# SuperPET_OS9_MMU_3_0.net
KiCad netlist of a schematic drawn in EAGLE
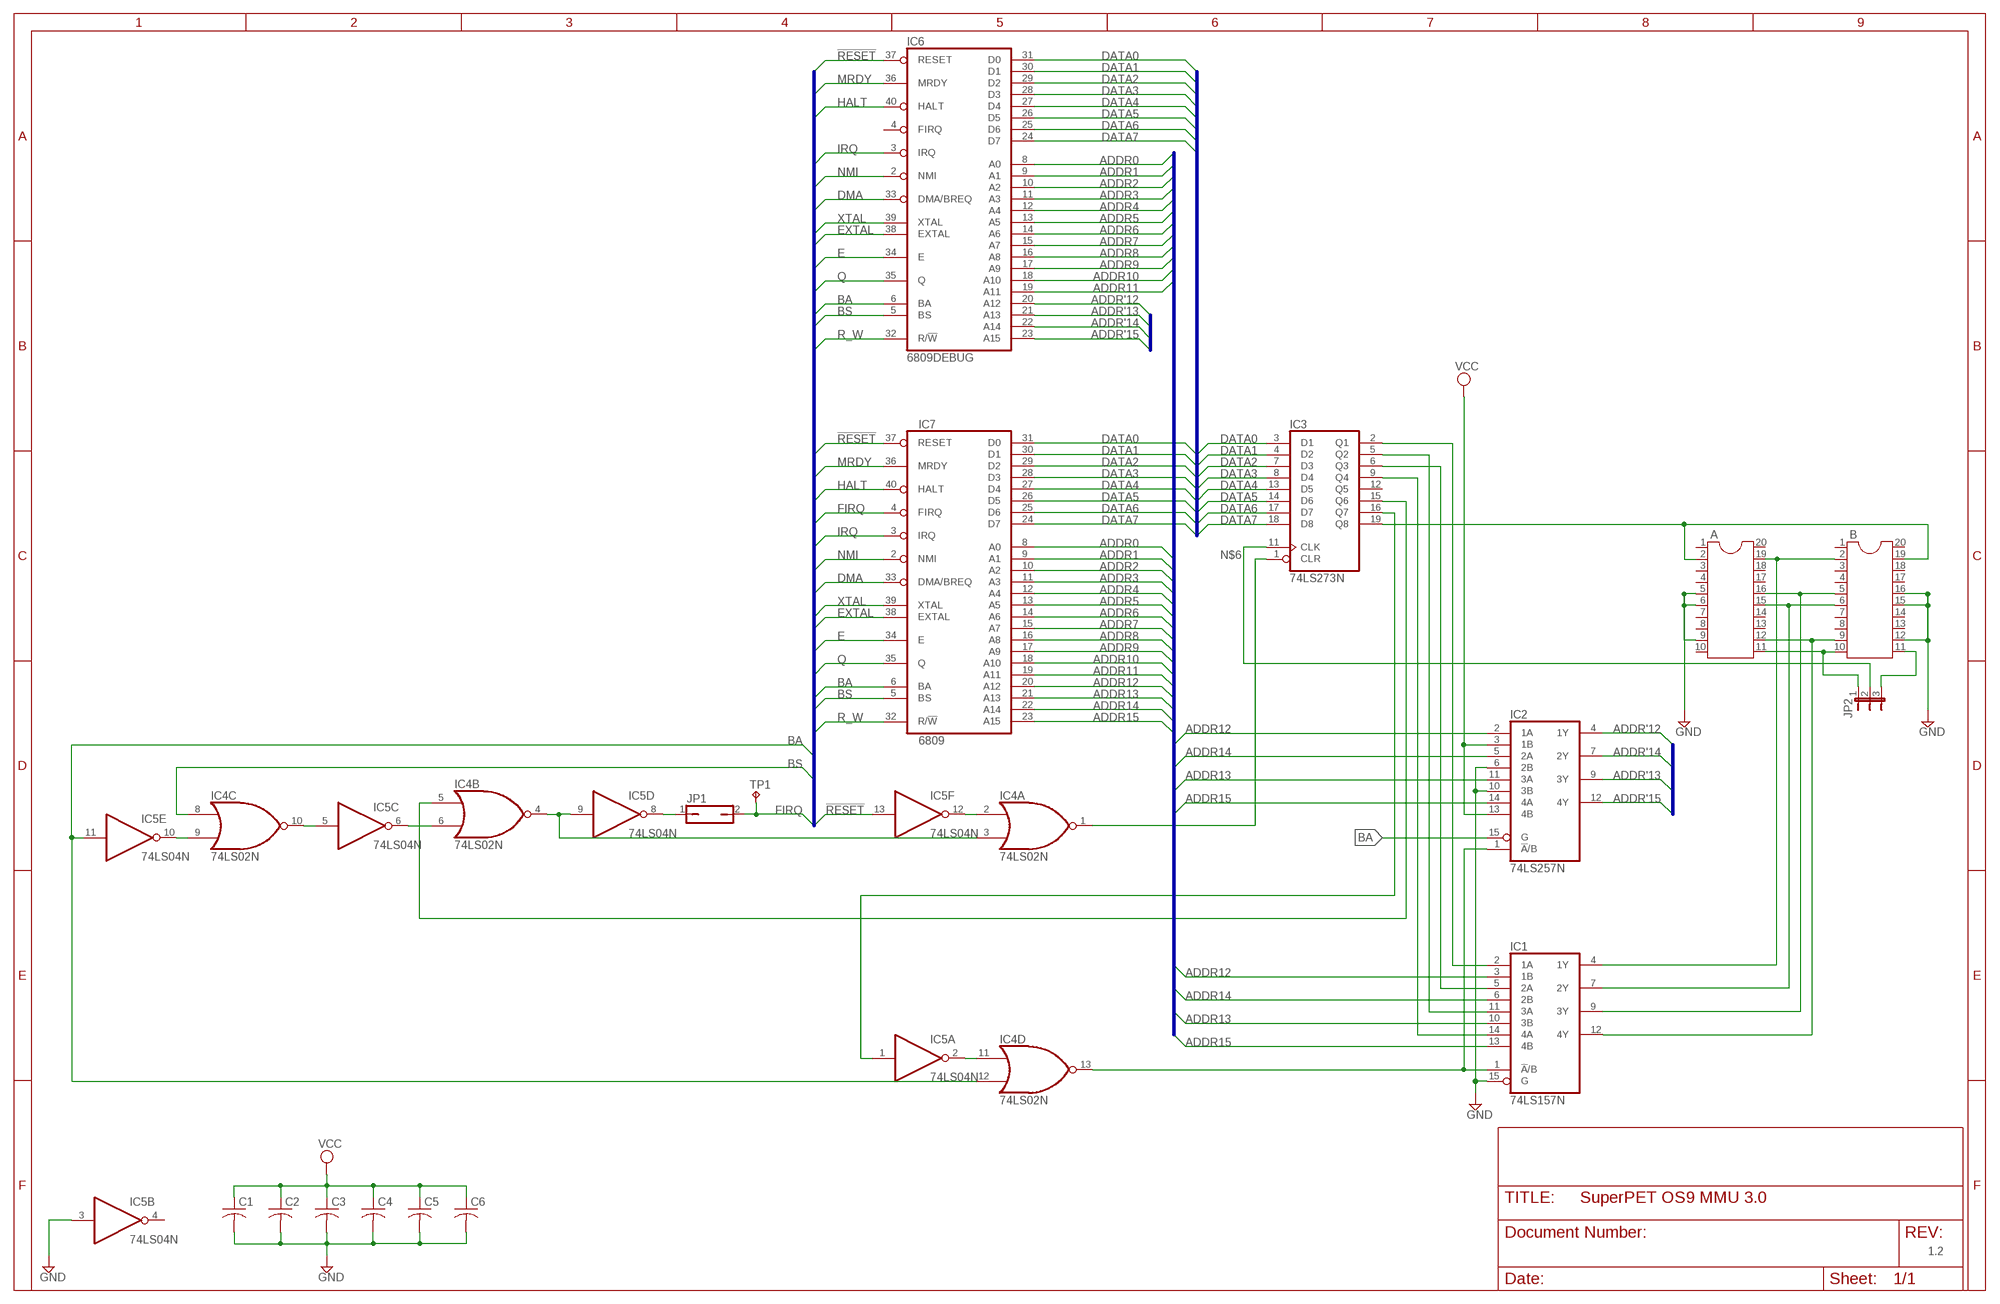
[diagram p0: schematic, sheet 1]

(export (version "E")
  (design (tool "Eeschema 10.0.6"))
  (components
    (comp (ref "A")
      (value "DIL20S")
      (footprint "eagle-import:SOCKET-20")
      (libsource (lib "eagle-import") (part "DIL20S"))
    )
    (comp (ref "B")
      (value "DIL20S")
      (footprint "eagle-import:SOCKET-20")
      (libsource (lib "eagle-import") (part "DIL20S"))
    )
    (comp (ref "C1")
      (value "C-US050-025X075")
      (footprint "eagle-import:C050-025X075")
      (libsource (lib "eagle-import") (part "C-US050-025X075"))
    )
    (comp (ref "C2")
      (value "C-US050-025X075")
      (footprint "eagle-import:C050-025X075")
      (libsource (lib "eagle-import") (part "C-US050-025X075"))
    )
    (comp (ref "C3")
      (value "C-US050-025X075")
      (footprint "eagle-import:C050-025X075")
      (libsource (lib "eagle-import") (part "C-US050-025X075"))
    )
    (comp (ref "C4")
      (value "C-US050-025X075")
      (footprint "eagle-import:C050-025X075")
      (libsource (lib "eagle-import") (part "C-US050-025X075"))
    )
    (comp (ref "C5")
      (value "C-US050-025X075")
      (footprint "eagle-import:C050-025X075")
      (libsource (lib "eagle-import") (part "C-US050-025X075"))
    )
    (comp (ref "C6")
      (value "C-US050-025X075")
      (footprint "eagle-import:C050-025X075")
      (libsource (lib "eagle-import") (part "C-US050-025X075"))
    )
    (comp (ref "IC1")
      (value "74LS157N")
      (footprint "eagle-import:DIL16")
      (libsource (lib "eagle-import") (part "74157NLS"))
    )
    (comp (ref "IC2")
      (value "74LS257N")
      (footprint "eagle-import:DIL16")
      (libsource (lib "eagle-import") (part "74257NLS"))
    )
    (comp (ref "IC3")
      (value "74LS273N")
      (footprint "eagle-import:DIL20")
      (libsource (lib "eagle-import") (part "74273N"))
    )
    (comp (ref "IC4")
      (value "74LS02N")
      (footprint "eagle-import:DIL14")
      (libsource (lib "eagle-import") (part "7402NLS"))
    )
    (comp (ref "IC5")
      (value "74LS04N")
      (footprint "eagle-import:DIL14")
      (libsource (lib "eagle-import") (part "7404NLS"))
    )
    (comp (ref "IC6")
      (value "6809DEBUG")
      (footprint "eagle-import:DIL40")
      (libsource (lib "eagle-import") (part "6809DEBUG"))
    )
    (comp (ref "IC7")
      (value "6809")
      (footprint "eagle-import:DIL40")
      (libsource (lib "eagle-import") (part "6809"))
    )
    (comp (ref "JP1")
      (value "JP1Q")
      (footprint "eagle-import:JP1")
      (libsource (lib "eagle-import") (part "JP1Q"))
    )
    (comp (ref "JP2")
      (value "JP2E")
      (footprint "eagle-import:JP2")
      (libsource (lib "eagle-import") (part "JP2E"))
    )
    (comp (ref "TP1")
      (value "TPPAD1-13")
      (footprint "eagle-import:P1-13")
      (libsource (lib "eagle-import") (part "TPPAD1-13"))
    )
  )
  (nets
    (net (code "1") (name "/ADDR'12") (class "Default")
      (node (ref "IC2") (pin "4") (pinfunction "1Y_4") (pintype "tri_state"))
      (node (ref "IC6") (pin "20") (pinfunction "A12_20") (pintype "tri_state"))
    )
    (net (code "2") (name "/ADDR'13") (class "Default")
      (node (ref "IC2") (pin "9") (pinfunction "3Y_9") (pintype "tri_state"))
      (node (ref "IC6") (pin "21") (pinfunction "A13_21") (pintype "tri_state"))
    )
    (net (code "3") (name "/ADDR'14") (class "Default")
      (node (ref "IC2") (pin "7") (pinfunction "2Y_7") (pintype "tri_state"))
      (node (ref "IC6") (pin "22") (pinfunction "A14_22") (pintype "tri_state"))
    )
    (net (code "4") (name "/ADDR'15") (class "Default")
      (node (ref "IC2") (pin "12") (pinfunction "4Y_12") (pintype "tri_state"))
      (node (ref "IC6") (pin "23") (pinfunction "A15_23") (pintype "tri_state"))
    )
    (net (code "5") (name "/ADDR0") (class "Default")
      (node (ref "IC6") (pin "8") (pinfunction "A0_8") (pintype "tri_state"))
      (node (ref "IC7") (pin "8") (pinfunction "A0_8") (pintype "tri_state"))
    )
    (net (code "6") (name "/ADDR1") (class "Default")
      (node (ref "IC6") (pin "9") (pinfunction "A1_9") (pintype "tri_state"))
      (node (ref "IC7") (pin "9") (pinfunction "A1_9") (pintype "tri_state"))
    )
    (net (code "7") (name "/ADDR2") (class "Default")
      (node (ref "IC6") (pin "10") (pinfunction "A2_10") (pintype "tri_state"))
      (node (ref "IC7") (pin "10") (pinfunction "A2_10") (pintype "tri_state"))
    )
    (net (code "8") (name "/ADDR3") (class "Default")
      (node (ref "IC6") (pin "11") (pinfunction "A3_11") (pintype "tri_state"))
      (node (ref "IC7") (pin "11") (pinfunction "A3_11") (pintype "tri_state"))
    )
    (net (code "9") (name "/ADDR4") (class "Default")
      (node (ref "IC6") (pin "12") (pinfunction "A4_12") (pintype "tri_state"))
      (node (ref "IC7") (pin "12") (pinfunction "A4_12") (pintype "tri_state"))
    )
    (net (code "10") (name "/ADDR5") (class "Default")
      (node (ref "IC6") (pin "13") (pinfunction "A5_13") (pintype "tri_state"))
      (node (ref "IC7") (pin "13") (pinfunction "A5_13") (pintype "tri_state"))
    )
    (net (code "11") (name "/ADDR6") (class "Default")
      (node (ref "IC6") (pin "14") (pinfunction "A6_14") (pintype "tri_state"))
      (node (ref "IC7") (pin "14") (pinfunction "A6_14") (pintype "tri_state"))
    )
    (net (code "12") (name "/ADDR7") (class "Default")
      (node (ref "IC6") (pin "15") (pinfunction "A7_15") (pintype "tri_state"))
      (node (ref "IC7") (pin "15") (pinfunction "A7_15") (pintype "tri_state"))
    )
    (net (code "13") (name "/ADDR8") (class "Default")
      (node (ref "IC6") (pin "16") (pinfunction "A8_16") (pintype "tri_state"))
      (node (ref "IC7") (pin "16") (pinfunction "A8_16") (pintype "tri_state"))
    )
    (net (code "14") (name "/ADDR9") (class "Default")
      (node (ref "IC6") (pin "17") (pinfunction "A9_17") (pintype "tri_state"))
      (node (ref "IC7") (pin "17") (pinfunction "A9_17") (pintype "tri_state"))
    )
    (net (code "15") (name "/ADDR10") (class "Default")
      (node (ref "IC6") (pin "18") (pinfunction "A10_18") (pintype "tri_state"))
      (node (ref "IC7") (pin "18") (pinfunction "A10_18") (pintype "tri_state"))
    )
    (net (code "16") (name "/ADDR11") (class "Default")
      (node (ref "IC6") (pin "19") (pinfunction "A11_19") (pintype "tri_state"))
      (node (ref "IC7") (pin "19") (pinfunction "A11_19") (pintype "tri_state"))
    )
    (net (code "17") (name "/ADDR12") (class "Default")
      (node (ref "IC1") (pin "3") (pinfunction "1B_3") (pintype "input"))
      (node (ref "IC2") (pin "2") (pinfunction "1A_2") (pintype "input"))
      (node (ref "IC7") (pin "20") (pinfunction "A12_20") (pintype "tri_state"))
    )
    (net (code "18") (name "/ADDR13") (class "Default")
      (node (ref "IC1") (pin "10") (pinfunction "3B_10") (pintype "input"))
      (node (ref "IC2") (pin "11") (pinfunction "3A_11") (pintype "input"))
      (node (ref "IC7") (pin "21") (pinfunction "A13_21") (pintype "tri_state"))
    )
    (net (code "19") (name "/ADDR14") (class "Default")
      (node (ref "IC1") (pin "6") (pinfunction "2B_6") (pintype "input"))
      (node (ref "IC2") (pin "5") (pinfunction "2A_5") (pintype "input"))
      (node (ref "IC7") (pin "22") (pinfunction "A14_22") (pintype "tri_state"))
    )
    (net (code "20") (name "/ADDR15") (class "Default")
      (node (ref "IC1") (pin "13") (pinfunction "4B_13") (pintype "input"))
      (node (ref "IC2") (pin "14") (pinfunction "4A_14") (pintype "input"))
      (node (ref "IC7") (pin "23") (pinfunction "A15_23") (pintype "tri_state"))
    )
    (net (code "21") (name "/BS") (class "Default")
      (node (ref "IC4") (pin "8") (pinfunction "I0_8") (pintype "input"))
      (node (ref "IC6") (pin "5") (pinfunction "BS_5") (pintype "input"))
      (node (ref "IC7") (pin "5") (pinfunction "BS_5") (pintype "output"))
    )
    (net (code "22") (name "/DATA0") (class "Default")
      (node (ref "IC3") (pin "3") (pinfunction "D1_3") (pintype "input"))
      (node (ref "IC6") (pin "31") (pinfunction "D0_31") (pintype "bidirectional"))
      (node (ref "IC7") (pin "31") (pinfunction "D0_31") (pintype "bidirectional"))
    )
    (net (code "23") (name "/DATA1") (class "Default")
      (node (ref "IC3") (pin "4") (pinfunction "D2_4") (pintype "input"))
      (node (ref "IC6") (pin "30") (pinfunction "D1_30") (pintype "bidirectional"))
      (node (ref "IC7") (pin "30") (pinfunction "D1_30") (pintype "bidirectional"))
    )
    (net (code "24") (name "/DATA2") (class "Default")
      (node (ref "IC3") (pin "7") (pinfunction "D3_7") (pintype "input"))
      (node (ref "IC6") (pin "29") (pinfunction "D2_29") (pintype "bidirectional"))
      (node (ref "IC7") (pin "29") (pinfunction "D2_29") (pintype "bidirectional"))
    )
    (net (code "25") (name "/DATA3") (class "Default")
      (node (ref "IC3") (pin "8") (pinfunction "D4_8") (pintype "input"))
      (node (ref "IC6") (pin "28") (pinfunction "D3_28") (pintype "bidirectional"))
      (node (ref "IC7") (pin "28") (pinfunction "D3_28") (pintype "bidirectional"))
    )
    (net (code "26") (name "/DATA4") (class "Default")
      (node (ref "IC3") (pin "13") (pinfunction "D5_13") (pintype "input"))
      (node (ref "IC6") (pin "27") (pinfunction "D4_27") (pintype "bidirectional"))
      (node (ref "IC7") (pin "27") (pinfunction "D4_27") (pintype "bidirectional"))
    )
    (net (code "27") (name "/DATA5") (class "Default")
      (node (ref "IC3") (pin "14") (pinfunction "D6_14") (pintype "input"))
      (node (ref "IC6") (pin "26") (pinfunction "D5_26") (pintype "bidirectional"))
      (node (ref "IC7") (pin "26") (pinfunction "D5_26") (pintype "bidirectional"))
    )
    (net (code "28") (name "/DATA6") (class "Default")
      (node (ref "IC3") (pin "17") (pinfunction "D7_17") (pintype "input"))
      (node (ref "IC6") (pin "25") (pinfunction "D6_25") (pintype "bidirectional"))
      (node (ref "IC7") (pin "25") (pinfunction "D6_25") (pintype "bidirectional"))
    )
    (net (code "29") (name "/DATA7") (class "Default")
      (node (ref "IC3") (pin "18") (pinfunction "D8_18") (pintype "input"))
      (node (ref "IC6") (pin "24") (pinfunction "D7_24") (pintype "bidirectional"))
      (node (ref "IC7") (pin "24") (pinfunction "D7_24") (pintype "bidirectional"))
    )
    (net (code "30") (name "/DMA") (class "Default")
      (node (ref "IC6") (pin "33") (pinfunction "DMA/BREQ_33") (pintype "output"))
      (node (ref "IC7") (pin "33") (pinfunction "DMA/BREQ_33") (pintype "input"))
    )
    (net (code "31") (name "/E") (class "Default")
      (node (ref "IC6") (pin "34") (pinfunction "E_34") (pintype "input"))
      (node (ref "IC7") (pin "34") (pinfunction "E_34") (pintype "output"))
    )
    (net (code "32") (name "/EXTAL") (class "Default")
      (node (ref "IC6") (pin "38") (pinfunction "EXTAL_38") (pintype "output"))
      (node (ref "IC7") (pin "38") (pinfunction "EXTAL_38") (pintype "input"))
    )
    (net (code "33") (name "/FIRQ") (class "Default")
      (node (ref "IC7") (pin "4") (pinfunction "FIRQ_4") (pintype "input"))
      (node (ref "JP1") (pin "2") (pinfunction "2_2") (pintype "passive"))
      (node (ref "TP1") (pin "1") (pinfunction "TP_1") (pintype "input"))
    )
    (net (code "34") (name "/HALT") (class "Default")
      (node (ref "IC6") (pin "40") (pinfunction "HALT_40") (pintype "output"))
      (node (ref "IC7") (pin "40") (pinfunction "HALT_40") (pintype "input"))
    )
    (net (code "35") (name "/IRQ") (class "Default")
      (node (ref "IC6") (pin "3") (pinfunction "IRQ_3") (pintype "output"))
      (node (ref "IC7") (pin "3") (pinfunction "IRQ_3") (pintype "input"))
    )
    (net (code "36") (name "/MRDY") (class "Default")
      (node (ref "IC6") (pin "36") (pinfunction "MRDY_36") (pintype "output"))
      (node (ref "IC7") (pin "36") (pinfunction "MRDY_36") (pintype "input"))
    )
    (net (code "37") (name "/N$6") (class "Default")
      (node (ref "IC3") (pin "1") (pinfunction "CLR_1") (pintype "input"))
      (node (ref "IC4") (pin "1") (pinfunction "O_1") (pintype "output"))
    )
    (net (code "38") (name "/NMI") (class "Default")
      (node (ref "IC6") (pin "2") (pinfunction "NMI_2") (pintype "output"))
      (node (ref "IC7") (pin "2") (pinfunction "NMI_2") (pintype "input"))
    )
    (net (code "39") (name "/Q") (class "Default")
      (node (ref "IC6") (pin "35") (pinfunction "Q_35") (pintype "input"))
      (node (ref "IC7") (pin "35") (pinfunction "Q_35") (pintype "output"))
    )
    (net (code "40") (name "/R_W") (class "Default")
      (node (ref "IC6") (pin "32") (pinfunction "R/~{W}_32") (pintype "input"))
      (node (ref "IC7") (pin "32") (pinfunction "R/~{W}_32") (pintype "output"))
    )
    (net (code "41") (name "/XTAL") (class "Default")
      (node (ref "IC6") (pin "39") (pinfunction "XTAL_39") (pintype "output"))
      (node (ref "IC7") (pin "39") (pinfunction "XTAL_39") (pintype "input"))
    )
    (net (code "42") (name "/~{RESET}") (class "Default")
      (node (ref "IC5") (pin "13") (pinfunction "I_13") (pintype "input"))
      (node (ref "IC6") (pin "37") (pinfunction "RESET_37") (pintype "output"))
      (node (ref "IC7") (pin "37") (pinfunction "RESET_37") (pintype "input"))
    )
    (net (code "43") (name "BA") (class "Default")
      (node (ref "IC2") (pin "15") (pinfunction "G_15") (pintype "input"))
      (node (ref "IC4") (pin "12") (pinfunction "I1_12") (pintype "input"))
      (node (ref "IC5") (pin "11") (pinfunction "I_11") (pintype "input"))
      (node (ref "IC6") (pin "6") (pinfunction "BA_6") (pintype "input"))
      (node (ref "IC7") (pin "6") (pinfunction "BA_6") (pintype "output"))
    )
    (net (code "44") (name "GND") (class "Default")
      (node (ref "A") (pin "5") (pinfunction "5_5") (pintype "passive"))
      (node (ref "A") (pin "6") (pinfunction "6_6") (pintype "passive"))
      (node (ref "A") (pin "9") (pinfunction "9_9") (pintype "passive"))
      (node (ref "B") (pin "12") (pinfunction "12_12") (pintype "passive"))
      (node (ref "B") (pin "15") (pinfunction "15_15") (pintype "passive"))
      (node (ref "B") (pin "16") (pinfunction "16_16") (pintype "passive"))
      (node (ref "C1") (pin "2") (pinfunction "2_2") (pintype "passive"))
      (node (ref "C2") (pin "2") (pinfunction "2_2") (pintype "passive"))
      (node (ref "C3") (pin "2") (pinfunction "2_2") (pintype "passive"))
      (node (ref "C4") (pin "2") (pinfunction "2_2") (pintype "passive"))
      (node (ref "C5") (pin "2") (pinfunction "2_2") (pintype "passive"))
      (node (ref "C6") (pin "2") (pinfunction "2_2") (pintype "passive"))
      (node (ref "IC1") (pin "15") (pinfunction "G_15") (pintype "input"))
      (node (ref "IC2") (pin "10") (pinfunction "3B_10") (pintype "input"))
      (node (ref "IC2") (pin "6") (pinfunction "2B_6") (pintype "input"))
      (node (ref "IC5") (pin "3") (pinfunction "I_3") (pintype "input"))
    )
    (net (code "45") (name "Net-(A-Pad11)") (class "Default")
      (node (ref "A") (pin "11") (pinfunction "11_11") (pintype "passive"))
      (node (ref "B") (pin "10") (pinfunction "10_10") (pintype "passive"))
      (node (ref "JP2") (pin "1") (pinfunction "1_1") (pintype "passive"))
    )
    (net (code "46") (name "Net-(B-Pad11)") (class "Default")
      (node (ref "B") (pin "11") (pinfunction "11_11") (pintype "passive"))
      (node (ref "JP2") (pin "3") (pinfunction "3_3") (pintype "passive"))
    )
    (net (code "47") (name "Net-(IC1A-1A)") (class "Default")
      (node (ref "IC1") (pin "2") (pinfunction "1A_2") (pintype "input"))
      (node (ref "IC3") (pin "2") (pinfunction "Q1_2") (pintype "output"))
    )
    (net (code "48") (name "Net-(IC1A-1Y)") (class "Default")
      (node (ref "A") (pin "19") (pinfunction "19_19") (pintype "passive"))
      (node (ref "B") (pin "2") (pinfunction "2_2") (pintype "passive"))
      (node (ref "IC1") (pin "4") (pinfunction "1Y_4") (pintype "output"))
    )
    (net (code "49") (name "Net-(IC1A-2A)") (class "Default")
      (node (ref "IC1") (pin "5") (pinfunction "2A_5") (pintype "input"))
      (node (ref "IC3") (pin "6") (pinfunction "Q3_6") (pintype "output"))
    )
    (net (code "50") (name "Net-(IC1A-2Y)") (class "Default")
      (node (ref "A") (pin "15") (pinfunction "15_15") (pintype "passive"))
      (node (ref "B") (pin "6") (pinfunction "6_6") (pintype "passive"))
      (node (ref "IC1") (pin "7") (pinfunction "2Y_7") (pintype "output"))
    )
    (net (code "51") (name "Net-(IC1A-3A)") (class "Default")
      (node (ref "IC1") (pin "11") (pinfunction "3A_11") (pintype "input"))
      (node (ref "IC3") (pin "5") (pinfunction "Q2_5") (pintype "output"))
    )
    (net (code "52") (name "Net-(IC1A-3Y)") (class "Default")
      (node (ref "A") (pin "16") (pinfunction "16_16") (pintype "passive"))
      (node (ref "B") (pin "5") (pinfunction "5_5") (pintype "passive"))
      (node (ref "IC1") (pin "9") (pinfunction "3Y_9") (pintype "output"))
    )
    (net (code "53") (name "Net-(IC1A-4A)") (class "Default")
      (node (ref "IC1") (pin "14") (pinfunction "4A_14") (pintype "input"))
      (node (ref "IC3") (pin "9") (pinfunction "Q4_9") (pintype "output"))
    )
    (net (code "54") (name "Net-(IC1A-4Y)") (class "Default")
      (node (ref "A") (pin "12") (pinfunction "12_12") (pintype "passive"))
      (node (ref "B") (pin "9") (pinfunction "9_9") (pintype "passive"))
      (node (ref "IC1") (pin "12") (pinfunction "4Y_12") (pintype "output"))
    )
    (net (code "55") (name "Net-(IC1A-~{A}{slash}B)") (class "Default")
      (node (ref "IC1") (pin "1") (pinfunction "~{A}/B_1") (pintype "input"))
      (node (ref "IC2") (pin "1") (pinfunction "~{A}/B_1") (pintype "input"))
      (node (ref "IC4") (pin "13") (pinfunction "O_13") (pintype "output"))
    )
    (net (code "56") (name "Net-(IC3A-CLK)") (class "Default")
      (node (ref "IC3") (pin "11") (pinfunction "CLK_11") (pintype "input"))
      (node (ref "JP2") (pin "2") (pinfunction "2_2") (pintype "passive"))
    )
    (net (code "57") (name "Net-(IC3A-Q6)") (class "Default")
      (node (ref "IC3") (pin "15") (pinfunction "Q6_15") (pintype "output"))
      (node (ref "IC4") (pin "5") (pinfunction "I0_5") (pintype "input"))
    )
    (net (code "58") (name "Net-(IC3A-Q7)") (class "Default")
      (node (ref "IC3") (pin "16") (pinfunction "Q7_16") (pintype "output"))
      (node (ref "IC5") (pin "1") (pinfunction "I_1") (pintype "input"))
    )
    (net (code "59") (name "Net-(IC3A-Q8)") (class "Default")
      (node (ref "A") (pin "2") (pinfunction "2_2") (pintype "passive"))
      (node (ref "B") (pin "19") (pinfunction "19_19") (pintype "passive"))
      (node (ref "IC3") (pin "19") (pinfunction "Q8_19") (pintype "output"))
    )
    (net (code "60") (name "Net-(IC4A-I0)") (class "Default")
      (node (ref "IC4") (pin "2") (pinfunction "I0_2") (pintype "input"))
      (node (ref "IC5") (pin "12") (pinfunction "O_12") (pintype "output"))
    )
    (net (code "61") (name "Net-(IC4A-I1)") (class "Default")
      (node (ref "IC4") (pin "3") (pinfunction "I1_3") (pintype "input"))
      (node (ref "IC4") (pin "4") (pinfunction "O_4") (pintype "output"))
      (node (ref "IC5") (pin "9") (pinfunction "I_9") (pintype "input"))
    )
    (net (code "62") (name "Net-(IC4B-I1)") (class "Default")
      (node (ref "IC4") (pin "6") (pinfunction "I1_6") (pintype "input"))
      (node (ref "IC5") (pin "6") (pinfunction "O_6") (pintype "output"))
    )
    (net (code "63") (name "Net-(IC4C-I1)") (class "Default")
      (node (ref "IC4") (pin "9") (pinfunction "I1_9") (pintype "input"))
      (node (ref "IC5") (pin "10") (pinfunction "O_10") (pintype "output"))
    )
    (net (code "64") (name "Net-(IC4C-O)") (class "Default")
      (node (ref "IC4") (pin "10") (pinfunction "O_10") (pintype "output"))
      (node (ref "IC5") (pin "5") (pinfunction "I_5") (pintype "input"))
    )
    (net (code "65") (name "Net-(IC4D-I0)") (class "Default")
      (node (ref "IC4") (pin "11") (pinfunction "I0_11") (pintype "input"))
      (node (ref "IC5") (pin "2") (pinfunction "O_2") (pintype "output"))
    )
    (net (code "66") (name "Net-(IC5D-O)") (class "Default")
      (node (ref "IC5") (pin "8") (pinfunction "O_8") (pintype "output"))
      (node (ref "JP1") (pin "1") (pinfunction "1_1") (pintype "passive"))
    )
    (net (code "67") (name "VCC") (class "Default")
      (node (ref "C1") (pin "1") (pinfunction "1_1") (pintype "passive"))
      (node (ref "C2") (pin "1") (pinfunction "1_1") (pintype "passive"))
      (node (ref "C3") (pin "1") (pinfunction "1_1") (pintype "passive"))
      (node (ref "C4") (pin "1") (pinfunction "1_1") (pintype "passive"))
      (node (ref "C5") (pin "1") (pinfunction "1_1") (pintype "passive"))
      (node (ref "C6") (pin "1") (pinfunction "1_1") (pintype "passive"))
      (node (ref "IC2") (pin "13") (pinfunction "4B_13") (pintype "input"))
      (node (ref "IC2") (pin "3") (pinfunction "1B_3") (pintype "input"))
    )
    (net (code "68") (name "unconnected-(A-Pad1)") (class "Default")
      (node (ref "A") (pin "1") (pinfunction "1_1") (pintype "passive"))
    )
    (net (code "69") (name "unconnected-(A-Pad3)") (class "Default")
      (node (ref "A") (pin "3") (pinfunction "3_3") (pintype "passive"))
    )
    (net (code "70") (name "unconnected-(A-Pad4)") (class "Default")
      (node (ref "A") (pin "4") (pinfunction "4_4") (pintype "passive"))
    )
    (net (code "71") (name "unconnected-(A-Pad7)") (class "Default")
      (node (ref "A") (pin "7") (pinfunction "7_7") (pintype "passive"))
    )
    (net (code "72") (name "unconnected-(A-Pad8)") (class "Default")
      (node (ref "A") (pin "8") (pinfunction "8_8") (pintype "passive"))
    )
    (net (code "73") (name "unconnected-(A-Pad10)") (class "Default")
      (node (ref "A") (pin "10") (pinfunction "10_10") (pintype "passive"))
    )
    (net (code "74") (name "unconnected-(A-Pad13)") (class "Default")
      (node (ref "A") (pin "13") (pinfunction "13_13") (pintype "passive"))
    )
    (net (code "75") (name "unconnected-(A-Pad14)") (class "Default")
      (node (ref "A") (pin "14") (pinfunction "14_14") (pintype "passive"))
    )
    (net (code "76") (name "unconnected-(A-Pad17)") (class "Default")
      (node (ref "A") (pin "17") (pinfunction "17_17") (pintype "passive"))
    )
    (net (code "77") (name "unconnected-(A-Pad18)") (class "Default")
      (node (ref "A") (pin "18") (pinfunction "18_18") (pintype "passive"))
    )
    (net (code "78") (name "unconnected-(A-Pad20)") (class "Default")
      (node (ref "A") (pin "20") (pinfunction "20_20") (pintype "passive"))
    )
    (net (code "79") (name "unconnected-(B-Pad1)") (class "Default")
      (node (ref "B") (pin "1") (pinfunction "1_1") (pintype "passive"))
    )
    (net (code "80") (name "unconnected-(B-Pad3)") (class "Default")
      (node (ref "B") (pin "3") (pinfunction "3_3") (pintype "passive"))
    )
    (net (code "81") (name "unconnected-(B-Pad4)") (class "Default")
      (node (ref "B") (pin "4") (pinfunction "4_4") (pintype "passive"))
    )
    (net (code "82") (name "unconnected-(B-Pad7)") (class "Default")
      (node (ref "B") (pin "7") (pinfunction "7_7") (pintype "passive"))
    )
    (net (code "83") (name "unconnected-(B-Pad8)") (class "Default")
      (node (ref "B") (pin "8") (pinfunction "8_8") (pintype "passive"))
    )
    (net (code "84") (name "unconnected-(B-Pad13)") (class "Default")
      (node (ref "B") (pin "13") (pinfunction "13_13") (pintype "passive"))
    )
    (net (code "85") (name "unconnected-(B-Pad14)") (class "Default")
      (node (ref "B") (pin "14") (pinfunction "14_14") (pintype "passive"))
    )
    (net (code "86") (name "unconnected-(B-Pad17)") (class "Default")
      (node (ref "B") (pin "17") (pinfunction "17_17") (pintype "passive"))
    )
    (net (code "87") (name "unconnected-(B-Pad18)") (class "Default")
      (node (ref "B") (pin "18") (pinfunction "18_18") (pintype "passive"))
    )
    (net (code "88") (name "unconnected-(B-Pad20)") (class "Default")
      (node (ref "B") (pin "20") (pinfunction "20_20") (pintype "passive"))
    )
    (net (code "89") (name "unconnected-(IC3A-Q5-Pad12)") (class "Default")
      (node (ref "IC3") (pin "12") (pinfunction "Q5_12") (pintype "output"))
    )
    (net (code "90") (name "unconnected-(IC5B-O-Pad4)") (class "Default")
      (node (ref "IC5") (pin "4") (pinfunction "O_4") (pintype "output"))
    )
    (net (code "91") (name "unconnected-(IC6A-FIRQ-Pad4)") (class "Default")
      (node (ref "IC6") (pin "4") (pinfunction "FIRQ_4") (pintype "output"))
    )
  )
)
